# RC-car-STM32.net
KiCad netlist of a schematic drawn in EAGLE
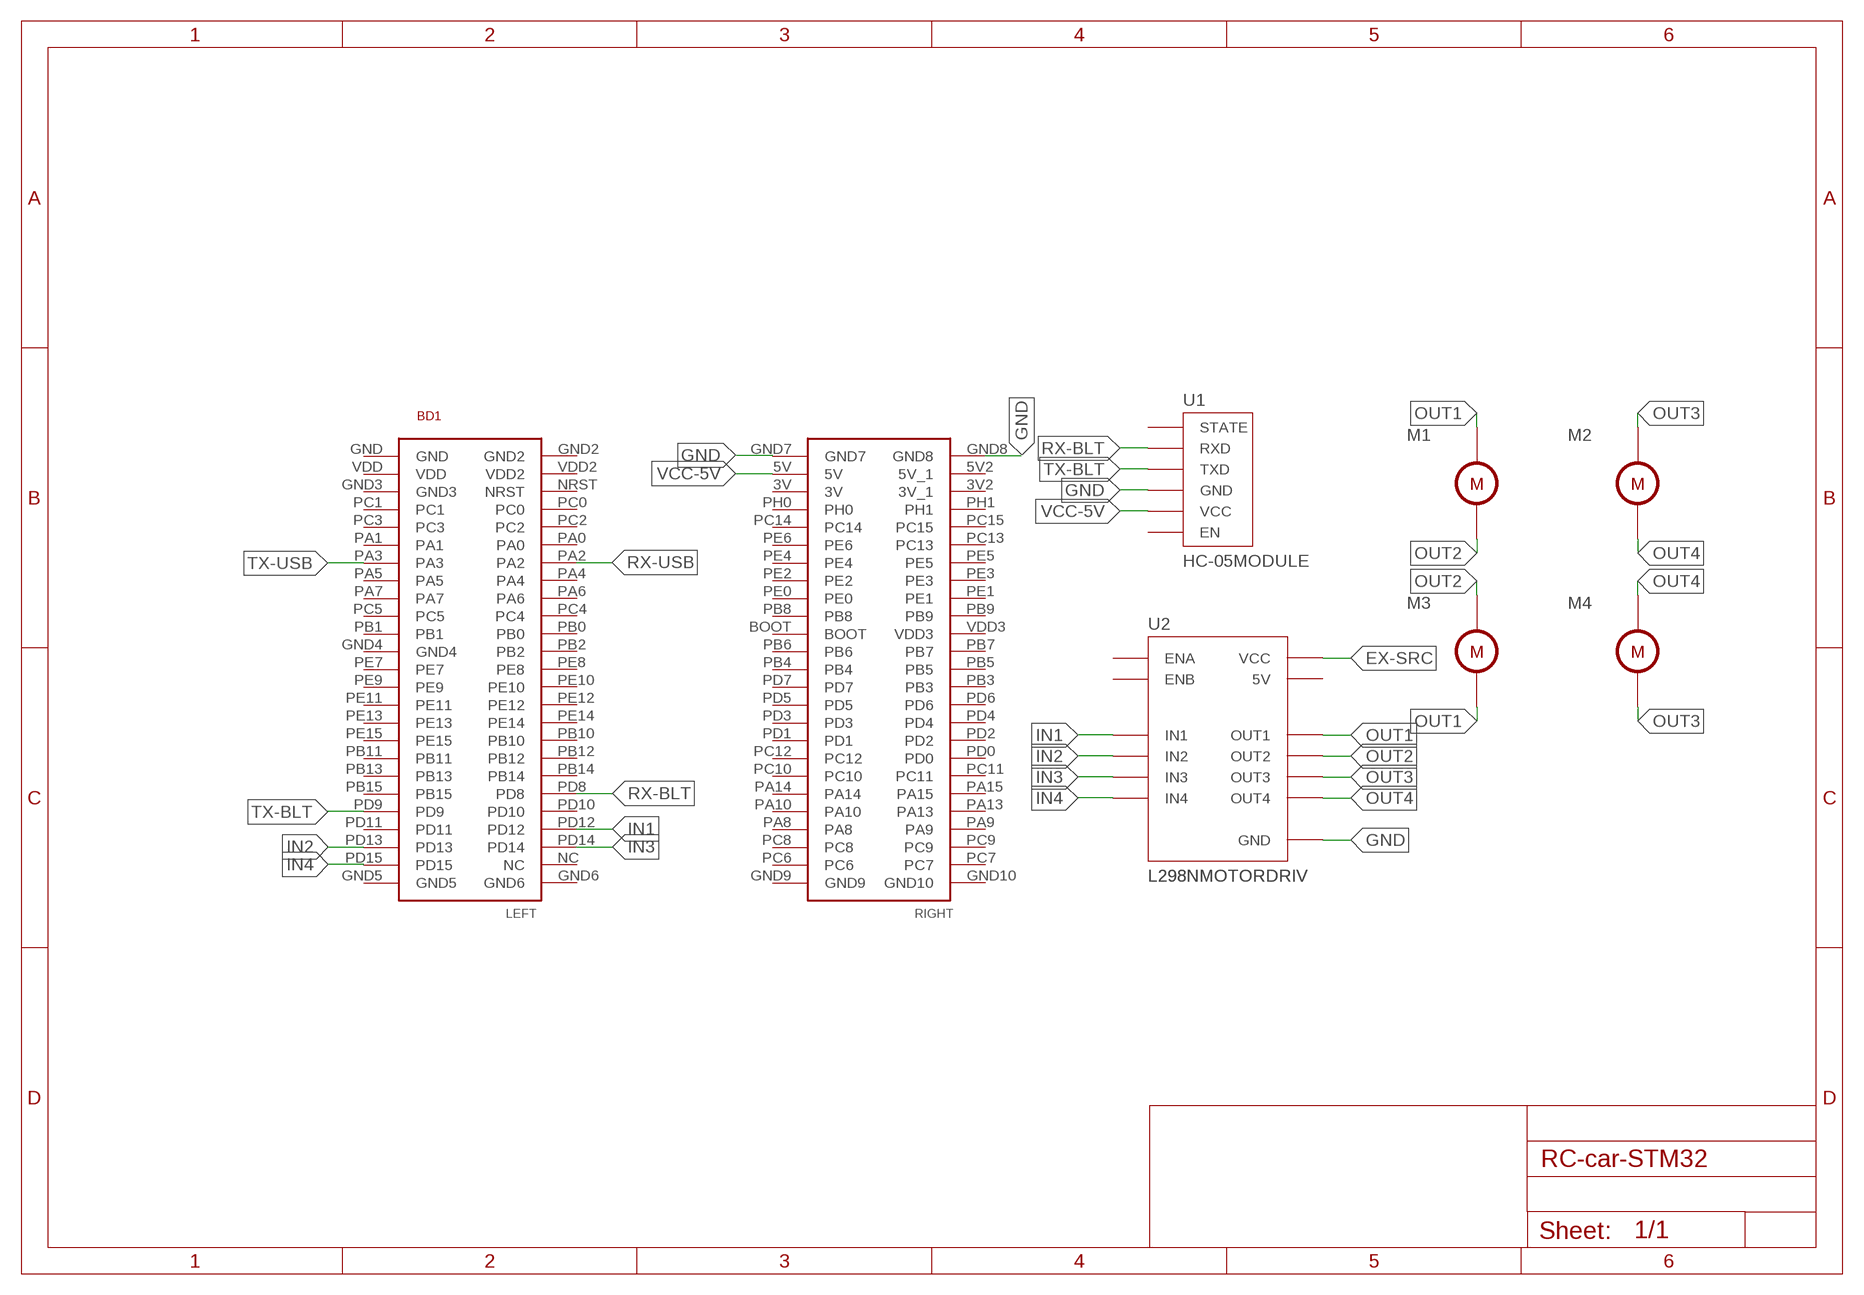
[diagram p0: schematic, sheet 1]

(export (version "E")
  (design (tool "Eeschema 10.0.6"))
  (components
    (comp (ref "BD1")
      (value "STM32F4-DISCOVERY")
      (footprint "eagle-import:STM32F407VG")
      (libsource (lib "eagle-import") (part "STM32F4-DISCOVERY"))
    )
    (comp (ref "M1")
      (value "DC-MOTOR")
      (footprint "eagle-import:DC-MOTOR")
      (libsource (lib "eagle-import") (part "DC-MOTOR"))
    )
    (comp (ref "M2")
      (value "DC-MOTOR")
      (footprint "eagle-import:DC-MOTOR")
      (libsource (lib "eagle-import") (part "DC-MOTOR"))
    )
    (comp (ref "M3")
      (value "DC-MOTOR")
      (footprint "eagle-import:DC-MOTOR")
      (libsource (lib "eagle-import") (part "DC-MOTOR"))
    )
    (comp (ref "M4")
      (value "DC-MOTOR")
      (footprint "eagle-import:DC-MOTOR")
      (libsource (lib "eagle-import") (part "DC-MOTOR"))
    )
    (comp (ref "U1")
      (value "HC-05MODULE")
      (footprint "eagle-import:HC-05MODULE")
      (libsource (lib "eagle-import") (part "HC-05MODULE"))
    )
    (comp (ref "U2")
      (value "L298NMOTORDRIV")
      (footprint "eagle-import:L289NMOTORDRIV")
      (libsource (lib "eagle-import") (part "L298NMOTORDRIV"))
    )
  )
  (nets
    (net (code "1") (name "EX-SRC") (class "Default")
      (node (ref "U2") (pin "VCC") (pinfunction "VCC_VCC") (pintype "bidirectional"))
    )
    (net (code "2") (name "GND") (class "Default")
      (node (ref "BD1") (pin "GND7") (pinfunction "GND7_GND7") (pintype "bidirectional"))
      (node (ref "BD1") (pin "GND8") (pinfunction "GND8_GND8") (pintype "bidirectional"))
      (node (ref "U1") (pin "GND") (pinfunction "GND_GND") (pintype "bidirectional"))
      (node (ref "U2") (pin "GND") (pinfunction "GND_GND") (pintype "bidirectional"))
    )
    (net (code "3") (name "IN1") (class "Default")
      (node (ref "BD1") (pin "PD12") (pinfunction "PD12_PD12") (pintype "bidirectional"))
      (node (ref "U2") (pin "IN1") (pinfunction "IN1_IN1") (pintype "bidirectional"))
    )
    (net (code "4") (name "IN2") (class "Default")
      (node (ref "BD1") (pin "PD13") (pinfunction "PD13_PD13") (pintype "bidirectional"))
      (node (ref "U2") (pin "IN2") (pinfunction "IN2_IN2") (pintype "bidirectional"))
    )
    (net (code "5") (name "IN3") (class "Default")
      (node (ref "BD1") (pin "PD14") (pinfunction "PD14_PD14") (pintype "bidirectional"))
      (node (ref "U2") (pin "IN3") (pinfunction "IN3_IN3") (pintype "bidirectional"))
    )
    (net (code "6") (name "IN4") (class "Default")
      (node (ref "BD1") (pin "PD15") (pinfunction "PD15_PD15") (pintype "bidirectional"))
      (node (ref "U2") (pin "IN4") (pinfunction "IN4_IN4") (pintype "bidirectional"))
    )
    (net (code "7") (name "OUT1") (class "Default")
      (node (ref "M1") (pin "+") (pinfunction "+_+") (pintype "bidirectional"))
      (node (ref "M3") (pin "-") (pinfunction "-_-") (pintype "bidirectional"))
      (node (ref "U2") (pin "OUT1") (pinfunction "OUT1_OUT1") (pintype "bidirectional"))
    )
    (net (code "8") (name "OUT2") (class "Default")
      (node (ref "M1") (pin "-") (pinfunction "-_-") (pintype "bidirectional"))
      (node (ref "M3") (pin "+") (pinfunction "+_+") (pintype "bidirectional"))
      (node (ref "U2") (pin "OUT2") (pinfunction "OUT2_OUT2") (pintype "bidirectional"))
    )
    (net (code "9") (name "OUT3") (class "Default")
      (node (ref "M2") (pin "+") (pinfunction "+_+") (pintype "bidirectional"))
      (node (ref "M4") (pin "-") (pinfunction "-_-") (pintype "bidirectional"))
      (node (ref "U2") (pin "OUT3") (pinfunction "OUT3_OUT3") (pintype "bidirectional"))
    )
    (net (code "10") (name "OUT4") (class "Default")
      (node (ref "M2") (pin "-") (pinfunction "-_-") (pintype "bidirectional"))
      (node (ref "M4") (pin "+") (pinfunction "+_+") (pintype "bidirectional"))
      (node (ref "U2") (pin "OUT4") (pinfunction "OUT4_OUT4") (pintype "bidirectional"))
    )
    (net (code "11") (name "RX-BLT") (class "Default")
      (node (ref "BD1") (pin "PD8") (pinfunction "PD8_PD8") (pintype "bidirectional"))
      (node (ref "U1") (pin "RXD") (pinfunction "RXD_RXD") (pintype "bidirectional"))
    )
    (net (code "12") (name "RX-USB") (class "Default")
      (node (ref "BD1") (pin "PA2") (pinfunction "PA2_PA2") (pintype "bidirectional"))
    )
    (net (code "13") (name "TX-BLT") (class "Default")
      (node (ref "BD1") (pin "PD9") (pinfunction "PD9_PD9") (pintype "bidirectional"))
      (node (ref "U1") (pin "TXD") (pinfunction "TXD_TXD") (pintype "bidirectional"))
    )
    (net (code "14") (name "TX-USB") (class "Default")
      (node (ref "BD1") (pin "PA3") (pinfunction "PA3_PA3") (pintype "bidirectional"))
    )
    (net (code "15") (name "VCC-5V") (class "Default")
      (node (ref "BD1") (pin "5V") (pinfunction "5V_5V") (pintype "bidirectional"))
      (node (ref "U1") (pin "VCC") (pinfunction "VCC_VCC") (pintype "bidirectional"))
    )
    (net (code "16") (name "unconnected-(BD1-3V_1-Pad3V2)") (class "Default")
      (node (ref "BD1") (pin "3V2") (pinfunction "3V_1_3V2") (pintype "bidirectional"))
    )
    (net (code "17") (name "unconnected-(BD1-5V_1-Pad5V2)") (class "Default")
      (node (ref "BD1") (pin "5V2") (pinfunction "5V_1_5V2") (pintype "bidirectional"))
    )
    (net (code "18") (name "unconnected-(BD1-Pad3V)") (class "Default")
      (node (ref "BD1") (pin "3V") (pinfunction "3V_3V") (pintype "bidirectional"))
    )
    (net (code "19") (name "unconnected-(BD1-PadBOOT)") (class "Default")
      (node (ref "BD1") (pin "BOOT") (pinfunction "BOOT_BOOT") (pintype "bidirectional"))
    )
    (net (code "20") (name "unconnected-(BD1-PadGND)") (class "Default")
      (node (ref "BD1") (pin "GND") (pinfunction "GND_GND") (pintype "bidirectional"))
    )
    (net (code "21") (name "unconnected-(BD1-PadGND2)") (class "Default")
      (node (ref "BD1") (pin "GND2") (pinfunction "GND2_GND2") (pintype "bidirectional"))
    )
    (net (code "22") (name "unconnected-(BD1-PadGND3)") (class "Default")
      (node (ref "BD1") (pin "GND3") (pinfunction "GND3_GND3") (pintype "bidirectional"))
    )
    (net (code "23") (name "unconnected-(BD1-PadGND4)") (class "Default")
      (node (ref "BD1") (pin "GND4") (pinfunction "GND4_GND4") (pintype "bidirectional"))
    )
    (net (code "24") (name "unconnected-(BD1-PadGND5)") (class "Default")
      (node (ref "BD1") (pin "GND5") (pinfunction "GND5_GND5") (pintype "bidirectional"))
    )
    (net (code "25") (name "unconnected-(BD1-PadGND6)") (class "Default")
      (node (ref "BD1") (pin "GND6") (pinfunction "GND6_GND6") (pintype "bidirectional"))
    )
    (net (code "26") (name "unconnected-(BD1-PadGND9)") (class "Default")
      (node (ref "BD1") (pin "GND9") (pinfunction "GND9_GND9") (pintype "bidirectional"))
    )
    (net (code "27") (name "unconnected-(BD1-PadGND10)") (class "Default")
      (node (ref "BD1") (pin "GND10") (pinfunction "GND10_GND10") (pintype "bidirectional"))
    )
    (net (code "28") (name "unconnected-(BD1-PadNC)") (class "Default")
      (node (ref "BD1") (pin "NC") (pinfunction "NC_NC") (pintype "bidirectional"))
    )
    (net (code "29") (name "unconnected-(BD1-PadNRST)") (class "Default")
      (node (ref "BD1") (pin "NRST") (pinfunction "NRST_NRST") (pintype "bidirectional"))
    )
    (net (code "30") (name "unconnected-(BD1-PadPA0)") (class "Default")
      (node (ref "BD1") (pin "PA0") (pinfunction "PA0_PA0") (pintype "bidirectional"))
    )
    (net (code "31") (name "unconnected-(BD1-PadPA1)") (class "Default")
      (node (ref "BD1") (pin "PA1") (pinfunction "PA1_PA1") (pintype "bidirectional"))
    )
    (net (code "32") (name "unconnected-(BD1-PadPA4)") (class "Default")
      (node (ref "BD1") (pin "PA4") (pinfunction "PA4_PA4") (pintype "bidirectional"))
    )
    (net (code "33") (name "unconnected-(BD1-PadPA5)") (class "Default")
      (node (ref "BD1") (pin "PA5") (pinfunction "PA5_PA5") (pintype "bidirectional"))
    )
    (net (code "34") (name "unconnected-(BD1-PadPA6)") (class "Default")
      (node (ref "BD1") (pin "PA6") (pinfunction "PA6_PA6") (pintype "bidirectional"))
    )
    (net (code "35") (name "unconnected-(BD1-PadPA7)") (class "Default")
      (node (ref "BD1") (pin "PA7") (pinfunction "PA7_PA7") (pintype "bidirectional"))
    )
    (net (code "36") (name "unconnected-(BD1-PadPA8)") (class "Default")
      (node (ref "BD1") (pin "PA8") (pinfunction "PA8_PA8") (pintype "bidirectional"))
    )
    (net (code "37") (name "unconnected-(BD1-PadPA9)") (class "Default")
      (node (ref "BD1") (pin "PA9") (pinfunction "PA9_PA9") (pintype "bidirectional"))
    )
    (net (code "38") (name "unconnected-(BD1-PadPA10)") (class "Default")
      (node (ref "BD1") (pin "PA10") (pinfunction "PA10_PA10") (pintype "bidirectional"))
    )
    (net (code "39") (name "unconnected-(BD1-PadPA13)") (class "Default")
      (node (ref "BD1") (pin "PA13") (pinfunction "PA13_PA13") (pintype "bidirectional"))
    )
    (net (code "40") (name "unconnected-(BD1-PadPA14)") (class "Default")
      (node (ref "BD1") (pin "PA14") (pinfunction "PA14_PA14") (pintype "bidirectional"))
    )
    (net (code "41") (name "unconnected-(BD1-PadPA15)") (class "Default")
      (node (ref "BD1") (pin "PA15") (pinfunction "PA15_PA15") (pintype "bidirectional"))
    )
    (net (code "42") (name "unconnected-(BD1-PadPB0)") (class "Default")
      (node (ref "BD1") (pin "PB0") (pinfunction "PB0_PB0") (pintype "bidirectional"))
    )
    (net (code "43") (name "unconnected-(BD1-PadPB1)") (class "Default")
      (node (ref "BD1") (pin "PB1") (pinfunction "PB1_PB1") (pintype "bidirectional"))
    )
    (net (code "44") (name "unconnected-(BD1-PadPB2)") (class "Default")
      (node (ref "BD1") (pin "PB2") (pinfunction "PB2_PB2") (pintype "bidirectional"))
    )
    (net (code "45") (name "unconnected-(BD1-PadPB3)") (class "Default")
      (node (ref "BD1") (pin "PB3") (pinfunction "PB3_PB3") (pintype "bidirectional"))
    )
    (net (code "46") (name "unconnected-(BD1-PadPB4)") (class "Default")
      (node (ref "BD1") (pin "PB4") (pinfunction "PB4_PB4") (pintype "bidirectional"))
    )
    (net (code "47") (name "unconnected-(BD1-PadPB5)") (class "Default")
      (node (ref "BD1") (pin "PB5") (pinfunction "PB5_PB5") (pintype "bidirectional"))
    )
    (net (code "48") (name "unconnected-(BD1-PadPB6)") (class "Default")
      (node (ref "BD1") (pin "PB6") (pinfunction "PB6_PB6") (pintype "bidirectional"))
    )
    (net (code "49") (name "unconnected-(BD1-PadPB7)") (class "Default")
      (node (ref "BD1") (pin "PB7") (pinfunction "PB7_PB7") (pintype "bidirectional"))
    )
    (net (code "50") (name "unconnected-(BD1-PadPB8)") (class "Default")
      (node (ref "BD1") (pin "PB8") (pinfunction "PB8_PB8") (pintype "bidirectional"))
    )
    (net (code "51") (name "unconnected-(BD1-PadPB9)") (class "Default")
      (node (ref "BD1") (pin "PB9") (pinfunction "PB9_PB9") (pintype "bidirectional"))
    )
    (net (code "52") (name "unconnected-(BD1-PadPB10)") (class "Default")
      (node (ref "BD1") (pin "PB10") (pinfunction "PB10_PB10") (pintype "bidirectional"))
    )
    (net (code "53") (name "unconnected-(BD1-PadPB11)") (class "Default")
      (node (ref "BD1") (pin "PB11") (pinfunction "PB11_PB11") (pintype "bidirectional"))
    )
    (net (code "54") (name "unconnected-(BD1-PadPB12)") (class "Default")
      (node (ref "BD1") (pin "PB12") (pinfunction "PB12_PB12") (pintype "bidirectional"))
    )
    (net (code "55") (name "unconnected-(BD1-PadPB13)") (class "Default")
      (node (ref "BD1") (pin "PB13") (pinfunction "PB13_PB13") (pintype "bidirectional"))
    )
    (net (code "56") (name "unconnected-(BD1-PadPB14)") (class "Default")
      (node (ref "BD1") (pin "PB14") (pinfunction "PB14_PB14") (pintype "bidirectional"))
    )
    (net (code "57") (name "unconnected-(BD1-PadPB15)") (class "Default")
      (node (ref "BD1") (pin "PB15") (pinfunction "PB15_PB15") (pintype "bidirectional"))
    )
    (net (code "58") (name "unconnected-(BD1-PadPC0)") (class "Default")
      (node (ref "BD1") (pin "PC0") (pinfunction "PC0_PC0") (pintype "bidirectional"))
    )
    (net (code "59") (name "unconnected-(BD1-PadPC1)") (class "Default")
      (node (ref "BD1") (pin "PC1") (pinfunction "PC1_PC1") (pintype "bidirectional"))
    )
    (net (code "60") (name "unconnected-(BD1-PadPC2)") (class "Default")
      (node (ref "BD1") (pin "PC2") (pinfunction "PC2_PC2") (pintype "bidirectional"))
    )
    (net (code "61") (name "unconnected-(BD1-PadPC3)") (class "Default")
      (node (ref "BD1") (pin "PC3") (pinfunction "PC3_PC3") (pintype "bidirectional"))
    )
    (net (code "62") (name "unconnected-(BD1-PadPC4)") (class "Default")
      (node (ref "BD1") (pin "PC4") (pinfunction "PC4_PC4") (pintype "bidirectional"))
    )
    (net (code "63") (name "unconnected-(BD1-PadPC5)") (class "Default")
      (node (ref "BD1") (pin "PC5") (pinfunction "PC5_PC5") (pintype "bidirectional"))
    )
    (net (code "64") (name "unconnected-(BD1-PadPC6)") (class "Default")
      (node (ref "BD1") (pin "PC6") (pinfunction "PC6_PC6") (pintype "bidirectional"))
    )
    (net (code "65") (name "unconnected-(BD1-PadPC7)") (class "Default")
      (node (ref "BD1") (pin "PC7") (pinfunction "PC7_PC7") (pintype "bidirectional"))
    )
    (net (code "66") (name "unconnected-(BD1-PadPC8)") (class "Default")
      (node (ref "BD1") (pin "PC8") (pinfunction "PC8_PC8") (pintype "bidirectional"))
    )
    (net (code "67") (name "unconnected-(BD1-PadPC9)") (class "Default")
      (node (ref "BD1") (pin "PC9") (pinfunction "PC9_PC9") (pintype "bidirectional"))
    )
    (net (code "68") (name "unconnected-(BD1-PadPC10)") (class "Default")
      (node (ref "BD1") (pin "PC10") (pinfunction "PC10_PC10") (pintype "bidirectional"))
    )
    (net (code "69") (name "unconnected-(BD1-PadPC11)") (class "Default")
      (node (ref "BD1") (pin "PC11") (pinfunction "PC11_PC11") (pintype "bidirectional"))
    )
    (net (code "70") (name "unconnected-(BD1-PadPC12)") (class "Default")
      (node (ref "BD1") (pin "PC12") (pinfunction "PC12_PC12") (pintype "bidirectional"))
    )
    (net (code "71") (name "unconnected-(BD1-PadPC13)") (class "Default")
      (node (ref "BD1") (pin "PC13") (pinfunction "PC13_PC13") (pintype "bidirectional"))
    )
    (net (code "72") (name "unconnected-(BD1-PadPC14)") (class "Default")
      (node (ref "BD1") (pin "PC14") (pinfunction "PC14_PC14") (pintype "bidirectional"))
    )
    (net (code "73") (name "unconnected-(BD1-PadPC15)") (class "Default")
      (node (ref "BD1") (pin "PC15") (pinfunction "PC15_PC15") (pintype "bidirectional"))
    )
    (net (code "74") (name "unconnected-(BD1-PadPD0)") (class "Default")
      (node (ref "BD1") (pin "PD0") (pinfunction "PD0_PD0") (pintype "bidirectional"))
    )
    (net (code "75") (name "unconnected-(BD1-PadPD1)") (class "Default")
      (node (ref "BD1") (pin "PD1") (pinfunction "PD1_PD1") (pintype "bidirectional"))
    )
    (net (code "76") (name "unconnected-(BD1-PadPD2)") (class "Default")
      (node (ref "BD1") (pin "PD2") (pinfunction "PD2_PD2") (pintype "bidirectional"))
    )
    (net (code "77") (name "unconnected-(BD1-PadPD3)") (class "Default")
      (node (ref "BD1") (pin "PD3") (pinfunction "PD3_PD3") (pintype "bidirectional"))
    )
    (net (code "78") (name "unconnected-(BD1-PadPD4)") (class "Default")
      (node (ref "BD1") (pin "PD4") (pinfunction "PD4_PD4") (pintype "bidirectional"))
    )
    (net (code "79") (name "unconnected-(BD1-PadPD5)") (class "Default")
      (node (ref "BD1") (pin "PD5") (pinfunction "PD5_PD5") (pintype "bidirectional"))
    )
    (net (code "80") (name "unconnected-(BD1-PadPD6)") (class "Default")
      (node (ref "BD1") (pin "PD6") (pinfunction "PD6_PD6") (pintype "bidirectional"))
    )
    (net (code "81") (name "unconnected-(BD1-PadPD7)") (class "Default")
      (node (ref "BD1") (pin "PD7") (pinfunction "PD7_PD7") (pintype "bidirectional"))
    )
    (net (code "82") (name "unconnected-(BD1-PadPD10)") (class "Default")
      (node (ref "BD1") (pin "PD10") (pinfunction "PD10_PD10") (pintype "bidirectional"))
    )
    (net (code "83") (name "unconnected-(BD1-PadPD11)") (class "Default")
      (node (ref "BD1") (pin "PD11") (pinfunction "PD11_PD11") (pintype "bidirectional"))
    )
    (net (code "84") (name "unconnected-(BD1-PadPE0)") (class "Default")
      (node (ref "BD1") (pin "PE0") (pinfunction "PE0_PE0") (pintype "bidirectional"))
    )
    (net (code "85") (name "unconnected-(BD1-PadPE1)") (class "Default")
      (node (ref "BD1") (pin "PE1") (pinfunction "PE1_PE1") (pintype "bidirectional"))
    )
    (net (code "86") (name "unconnected-(BD1-PadPE2)") (class "Default")
      (node (ref "BD1") (pin "PE2") (pinfunction "PE2_PE2") (pintype "bidirectional"))
    )
    (net (code "87") (name "unconnected-(BD1-PadPE3)") (class "Default")
      (node (ref "BD1") (pin "PE3") (pinfunction "PE3_PE3") (pintype "bidirectional"))
    )
    (net (code "88") (name "unconnected-(BD1-PadPE4)") (class "Default")
      (node (ref "BD1") (pin "PE4") (pinfunction "PE4_PE4") (pintype "bidirectional"))
    )
    (net (code "89") (name "unconnected-(BD1-PadPE5)") (class "Default")
      (node (ref "BD1") (pin "PE5") (pinfunction "PE5_PE5") (pintype "bidirectional"))
    )
    (net (code "90") (name "unconnected-(BD1-PadPE6)") (class "Default")
      (node (ref "BD1") (pin "PE6") (pinfunction "PE6_PE6") (pintype "bidirectional"))
    )
    (net (code "91") (name "unconnected-(BD1-PadPE7)") (class "Default")
      (node (ref "BD1") (pin "PE7") (pinfunction "PE7_PE7") (pintype "bidirectional"))
    )
    (net (code "92") (name "unconnected-(BD1-PadPE8)") (class "Default")
      (node (ref "BD1") (pin "PE8") (pinfunction "PE8_PE8") (pintype "bidirectional"))
    )
    (net (code "93") (name "unconnected-(BD1-PadPE9)") (class "Default")
      (node (ref "BD1") (pin "PE9") (pinfunction "PE9_PE9") (pintype "bidirectional"))
    )
    (net (code "94") (name "unconnected-(BD1-PadPE10)") (class "Default")
      (node (ref "BD1") (pin "PE10") (pinfunction "PE10_PE10") (pintype "bidirectional"))
    )
    (net (code "95") (name "unconnected-(BD1-PadPE11)") (class "Default")
      (node (ref "BD1") (pin "PE11") (pinfunction "PE11_PE11") (pintype "bidirectional"))
    )
    (net (code "96") (name "unconnected-(BD1-PadPE12)") (class "Default")
      (node (ref "BD1") (pin "PE12") (pinfunction "PE12_PE12") (pintype "bidirectional"))
    )
    (net (code "97") (name "unconnected-(BD1-PadPE13)") (class "Default")
      (node (ref "BD1") (pin "PE13") (pinfunction "PE13_PE13") (pintype "bidirectional"))
    )
    (net (code "98") (name "unconnected-(BD1-PadPE14)") (class "Default")
      (node (ref "BD1") (pin "PE14") (pinfunction "PE14_PE14") (pintype "bidirectional"))
    )
    (net (code "99") (name "unconnected-(BD1-PadPE15)") (class "Default")
      (node (ref "BD1") (pin "PE15") (pinfunction "PE15_PE15") (pintype "bidirectional"))
    )
    (net (code "100") (name "unconnected-(BD1-PadPH0)") (class "Default")
      (node (ref "BD1") (pin "PH0") (pinfunction "PH0_PH0") (pintype "bidirectional"))
    )
    (net (code "101") (name "unconnected-(BD1-PadPH1)") (class "Default")
      (node (ref "BD1") (pin "PH1") (pinfunction "PH1_PH1") (pintype "bidirectional"))
    )
    (net (code "102") (name "unconnected-(BD1-PadVDD)") (class "Default")
      (node (ref "BD1") (pin "VDD") (pinfunction "VDD_VDD") (pintype "bidirectional"))
    )
    (net (code "103") (name "unconnected-(BD1-PadVDD2)") (class "Default")
      (node (ref "BD1") (pin "VDD2") (pinfunction "VDD2_VDD2") (pintype "bidirectional"))
    )
    (net (code "104") (name "unconnected-(BD1-PadVDD3)") (class "Default")
      (node (ref "BD1") (pin "VDD3") (pinfunction "VDD3_VDD3") (pintype "bidirectional"))
    )
    (net (code "105") (name "unconnected-(U1-PadEN)") (class "Default")
      (node (ref "U1") (pin "EN") (pinfunction "EN_EN") (pintype "bidirectional"))
    )
    (net (code "106") (name "unconnected-(U1-PadSTATE)") (class "Default")
      (node (ref "U1") (pin "STATE") (pinfunction "STATE_STATE") (pintype "bidirectional"))
    )
    (net (code "107") (name "unconnected-(U2-Pad5V)") (class "Default")
      (node (ref "U2") (pin "5V") (pinfunction "5V_5V") (pintype "bidirectional"))
    )
    (net (code "108") (name "unconnected-(U2-PadENA)") (class "Default")
      (node (ref "U2") (pin "ENA") (pinfunction "ENA_ENA") (pintype "bidirectional"))
    )
    (net (code "109") (name "unconnected-(U2-PadENB)") (class "Default")
      (node (ref "U2") (pin "ENB") (pinfunction "ENB_ENB") (pintype "bidirectional"))
    )
  )
)
